# control_board_schematic.net
KiCad netlist of a schematic drawn in EasyEDA
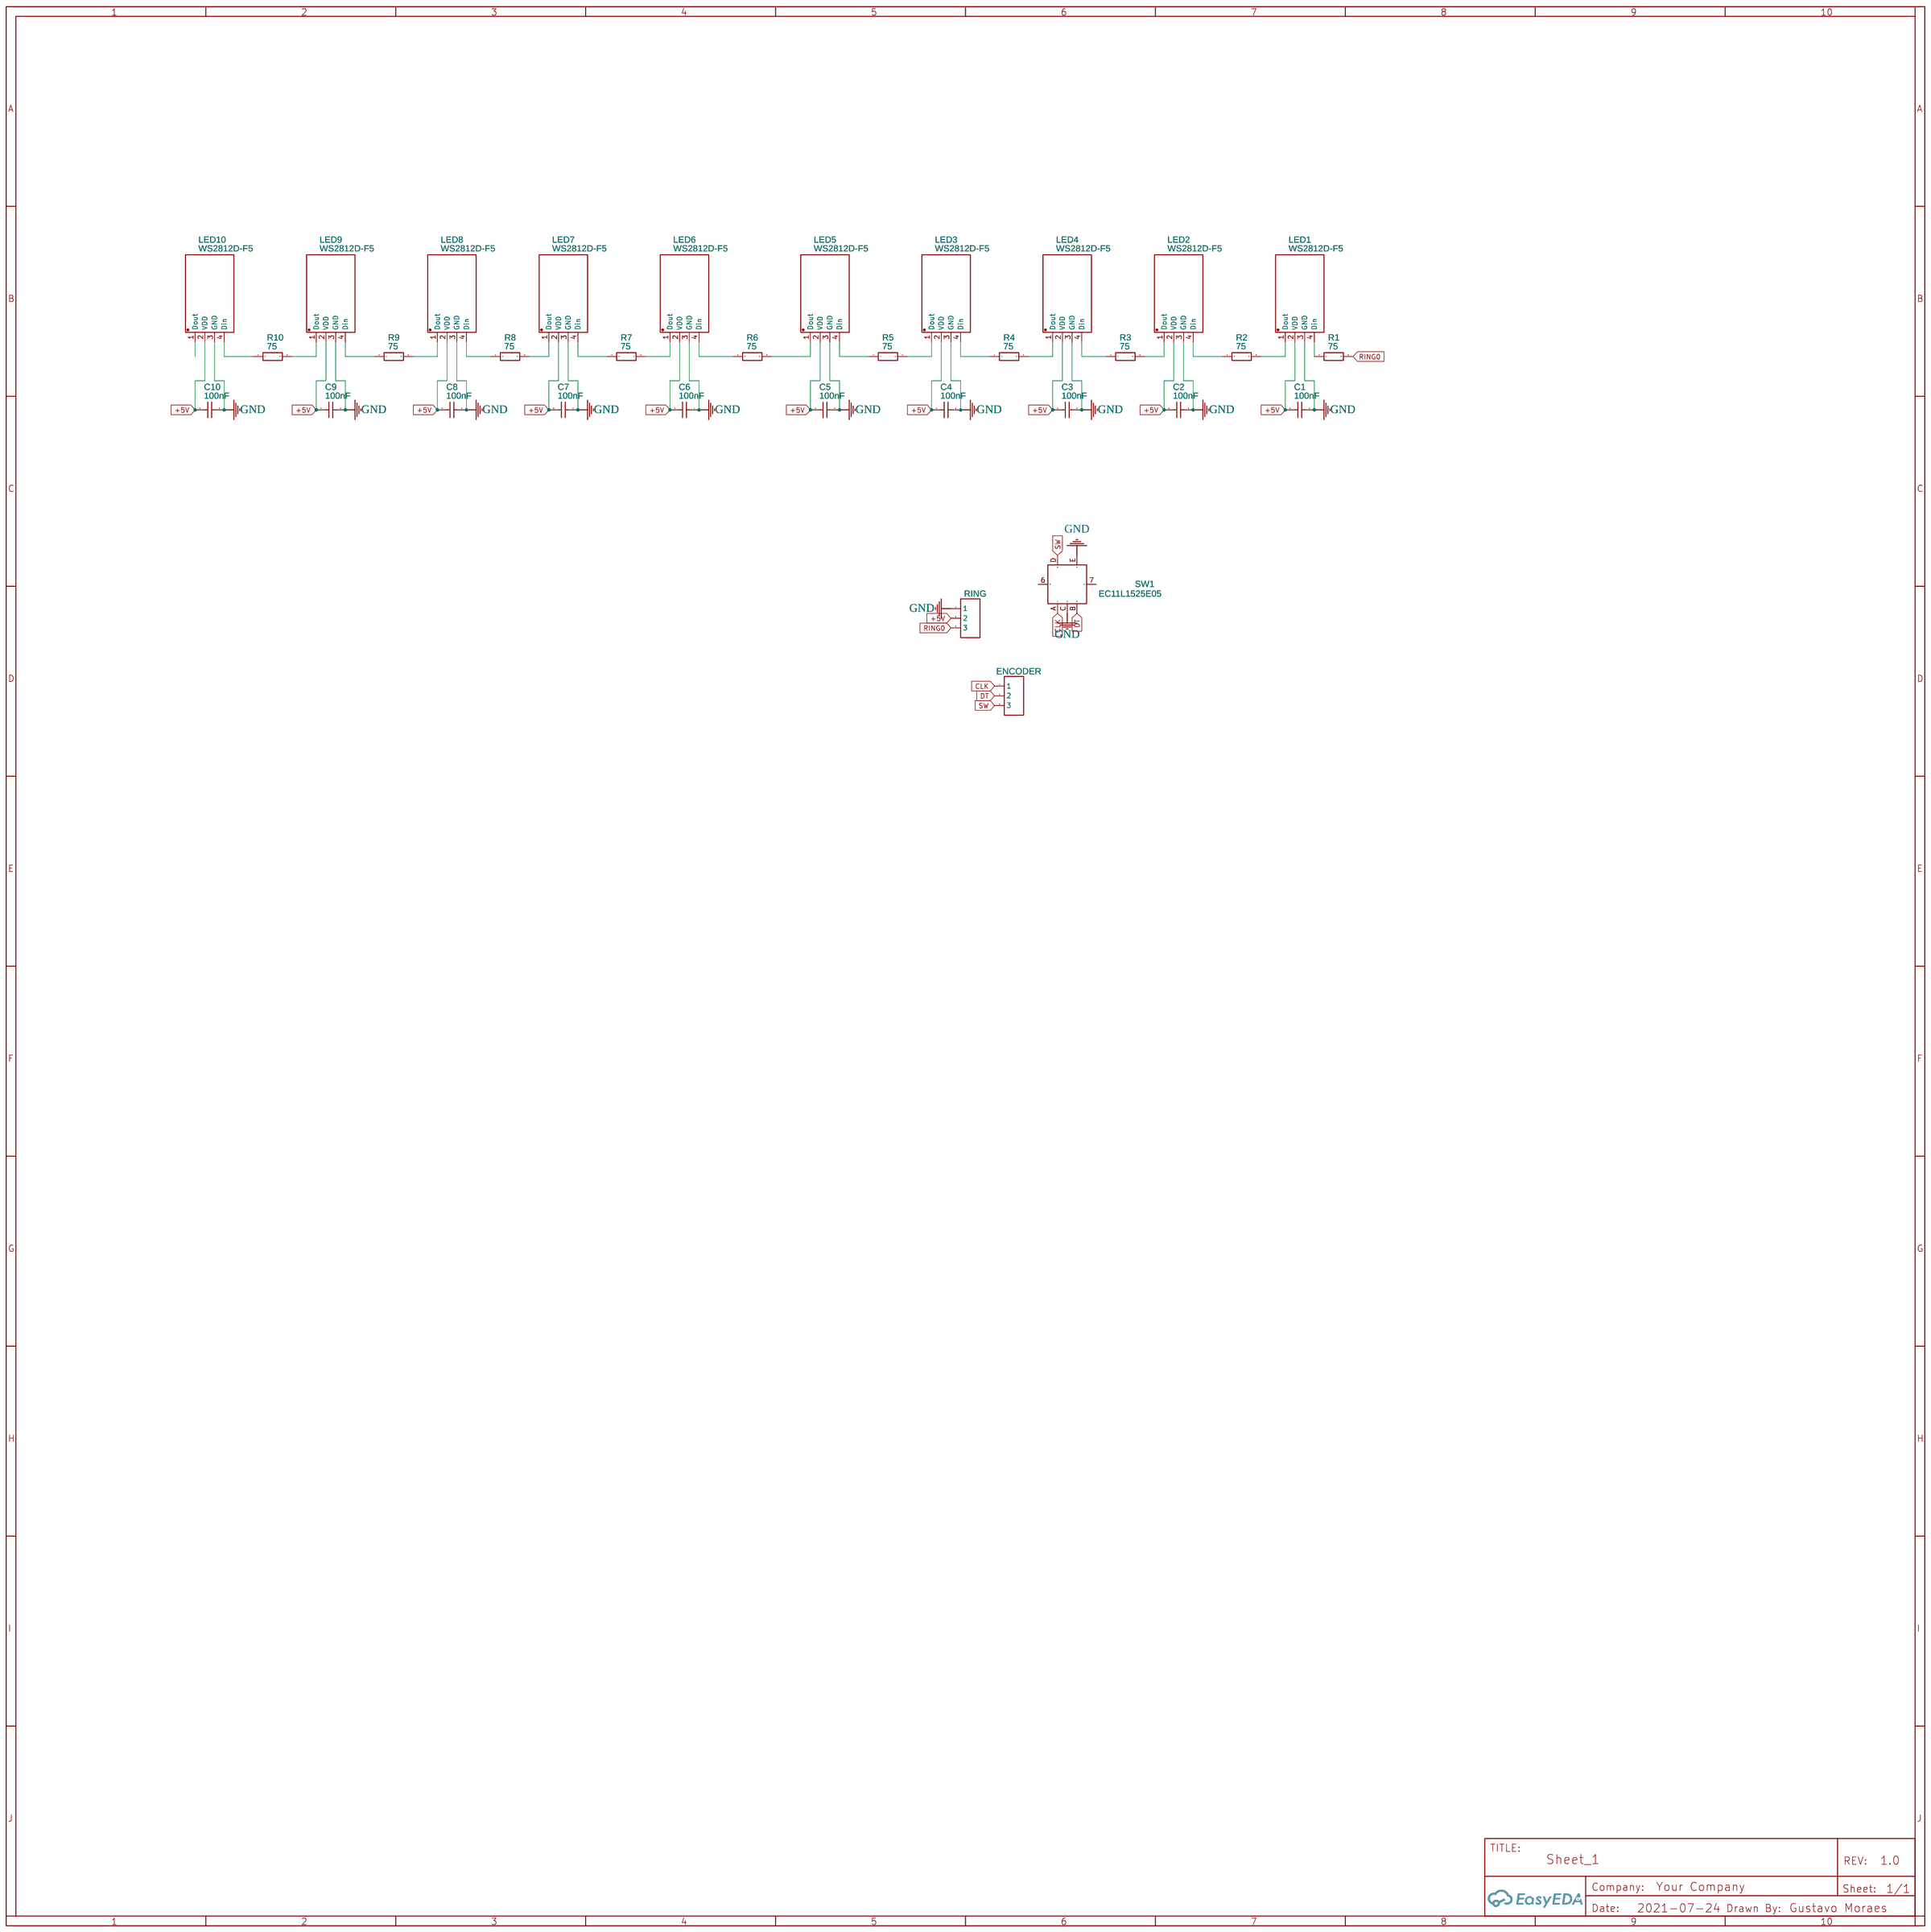
[diagram p0: schematic sheet]

(export (version "E")
  (design (tool "Eeschema 10.0.6"))
  (components
    (comp (ref "C1")
      (value "100nF")
      (fields
        (field (name "BOM_Manufacturer Part") "0603B104K160")
        (field (name "BOM_Supplier Part") "C80516")
      )
      (libsource (lib "") (part "0603B104K160"))
    )
    (comp (ref "C2")
      (value "100nF")
      (fields
        (field (name "BOM_Manufacturer Part") "0603B104K160")
        (field (name "BOM_Supplier Part") "C80516")
      )
      (libsource (lib "") (part "0603B104K160"))
    )
    (comp (ref "C3")
      (value "100nF")
      (fields
        (field (name "BOM_Manufacturer Part") "0603B104K160")
        (field (name "BOM_Supplier Part") "C80516")
      )
      (libsource (lib "") (part "0603B104K160"))
    )
    (comp (ref "C4")
      (value "100nF")
      (fields
        (field (name "BOM_Manufacturer Part") "0603B104K160")
        (field (name "BOM_Supplier Part") "C80516")
      )
      (libsource (lib "") (part "0603B104K160"))
    )
    (comp (ref "C5")
      (value "100nF")
      (fields
        (field (name "BOM_Manufacturer Part") "0603B104K160")
        (field (name "BOM_Supplier Part") "C80516")
      )
      (libsource (lib "") (part "0603B104K160"))
    )
    (comp (ref "C6")
      (value "100nF")
      (fields
        (field (name "BOM_Manufacturer Part") "0603B104K160")
        (field (name "BOM_Supplier Part") "C80516")
      )
      (libsource (lib "") (part "0603B104K160"))
    )
    (comp (ref "C7")
      (value "100nF")
      (fields
        (field (name "BOM_Manufacturer Part") "0603B104K160")
        (field (name "BOM_Supplier Part") "C80516")
      )
      (libsource (lib "") (part "0603B104K160"))
    )
    (comp (ref "C8")
      (value "100nF")
      (fields
        (field (name "BOM_Manufacturer Part") "0603B104K160")
        (field (name "BOM_Supplier Part") "C80516")
      )
      (libsource (lib "") (part "0603B104K160"))
    )
    (comp (ref "C9")
      (value "100nF")
      (fields
        (field (name "BOM_Manufacturer Part") "0603B104K160")
        (field (name "BOM_Supplier Part") "C80516")
      )
      (libsource (lib "") (part "0603B104K160"))
    )
    (comp (ref "C10")
      (value "100nF")
      (fields
        (field (name "BOM_Manufacturer Part") "0603B104K160")
        (field (name "BOM_Supplier Part") "C80516")
      )
      (libsource (lib "") (part "0603B104K160"))
    )
    (comp (ref "ENCODER")
      (value "HDR-M-2.54_1x3")
      (fields (field (name "BOM_Supplier Part") "C180248"))
      (libsource (lib "") (part "HDR-M-2.54_1x3_1"))
    )
    (comp (ref "LED1")
      (value "WS2812D-F5")
      (fields (field (name "BOM_Supplier Part") "C190565"))
      (libsource (lib "") (part "WS2812D-F5"))
    )
    (comp (ref "LED2")
      (value "WS2812D-F5")
      (fields (field (name "BOM_Supplier Part") "C190565"))
      (libsource (lib "") (part "WS2812D-F5"))
    )
    (comp (ref "LED3")
      (value "WS2812D-F5")
      (fields (field (name "BOM_Supplier Part") "C190565"))
      (libsource (lib "") (part "WS2812D-F5"))
    )
    (comp (ref "LED4")
      (value "WS2812D-F5")
      (fields (field (name "BOM_Supplier Part") "C190565"))
      (libsource (lib "") (part "WS2812D-F5"))
    )
    (comp (ref "LED5")
      (value "WS2812D-F5")
      (fields (field (name "BOM_Supplier Part") "C190565"))
      (libsource (lib "") (part "WS2812D-F5"))
    )
    (comp (ref "LED6")
      (value "WS2812D-F5")
      (fields (field (name "BOM_Supplier Part") "C190565"))
      (libsource (lib "") (part "WS2812D-F5"))
    )
    (comp (ref "LED7")
      (value "WS2812D-F5")
      (fields (field (name "BOM_Supplier Part") "C190565"))
      (libsource (lib "") (part "WS2812D-F5"))
    )
    (comp (ref "LED8")
      (value "WS2812D-F5")
      (fields (field (name "BOM_Supplier Part") "C190565"))
      (libsource (lib "") (part "WS2812D-F5"))
    )
    (comp (ref "LED9")
      (value "WS2812D-F5")
      (fields (field (name "BOM_Supplier Part") "C190565"))
      (libsource (lib "") (part "WS2812D-F5"))
    )
    (comp (ref "LED10")
      (value "WS2812D-F5")
      (fields (field (name "BOM_Supplier Part") "C190565"))
      (libsource (lib "") (part "WS2812D-F5"))
    )
    (comp (ref "R1")
      (value "75")
      (fields
        (field (name "BOM_Manufacturer Part") "RC0805JR-0775RL")
        (field (name "BOM_Supplier Part") "C113304")
      )
      (libsource (lib "") (part "RC0805JR-0775RL"))
    )
    (comp (ref "R2")
      (value "75")
      (fields
        (field (name "BOM_Manufacturer Part") "RC0805JR-0775RL")
        (field (name "BOM_Supplier Part") "C113304")
      )
      (libsource (lib "") (part "RC0805JR-0775RL"))
    )
    (comp (ref "R3")
      (value "75")
      (fields
        (field (name "BOM_Manufacturer Part") "RC0805JR-0775RL")
        (field (name "BOM_Supplier Part") "C113304")
      )
      (libsource (lib "") (part "RC0805JR-0775RL"))
    )
    (comp (ref "R4")
      (value "75")
      (fields
        (field (name "BOM_Manufacturer Part") "RC0805JR-0775RL")
        (field (name "BOM_Supplier Part") "C113304")
      )
      (libsource (lib "") (part "RC0805JR-0775RL"))
    )
    (comp (ref "R5")
      (value "75")
      (fields
        (field (name "BOM_Manufacturer Part") "RC0805JR-0775RL")
        (field (name "BOM_Supplier Part") "C113304")
      )
      (libsource (lib "") (part "RC0805JR-0775RL"))
    )
    (comp (ref "R6")
      (value "75")
      (fields
        (field (name "BOM_Manufacturer Part") "RC0805JR-0775RL")
        (field (name "BOM_Supplier Part") "C113304")
      )
      (libsource (lib "") (part "RC0805JR-0775RL"))
    )
    (comp (ref "R7")
      (value "75")
      (fields
        (field (name "BOM_Manufacturer Part") "RC0805JR-0775RL")
        (field (name "BOM_Supplier Part") "C113304")
      )
      (libsource (lib "") (part "RC0805JR-0775RL"))
    )
    (comp (ref "R8")
      (value "75")
      (fields
        (field (name "BOM_Manufacturer Part") "RC0805JR-0775RL")
        (field (name "BOM_Supplier Part") "C113304")
      )
      (libsource (lib "") (part "RC0805JR-0775RL"))
    )
    (comp (ref "R9")
      (value "75")
      (fields
        (field (name "BOM_Manufacturer Part") "RC0805JR-0775RL")
        (field (name "BOM_Supplier Part") "C113304")
      )
      (libsource (lib "") (part "RC0805JR-0775RL"))
    )
    (comp (ref "R10")
      (value "75")
      (fields
        (field (name "BOM_Manufacturer Part") "RC0805JR-0775RL")
        (field (name "BOM_Supplier Part") "C113304")
      )
      (libsource (lib "") (part "RC0805JR-0775RL"))
    )
    (comp (ref "RING")
      (value "HDR-M-2.54_1x3")
      (fields (field (name "BOM_Supplier Part") "C180248"))
      (libsource (lib "") (part "HDR-M-2.54_1x3"))
    )
    (comp (ref "SW1")
      (value "EC11L1525E05")
      (fields (field (name "BOM_Supplier Part") "C2687298"))
      (libsource (lib "") (part "EC11L1525E05"))
    )
  )
  (nets
    (net (code "1") (name "+5V") (class "Default")
      (node (ref "C1") (pin "2") (pinfunction "2_2") (pintype "input"))
      (node (ref "C10") (pin "2") (pinfunction "2_2") (pintype "input"))
      (node (ref "C2") (pin "2") (pinfunction "2_2") (pintype "input"))
      (node (ref "C3") (pin "2") (pinfunction "2_2") (pintype "input"))
      (node (ref "C4") (pin "2") (pinfunction "2_2") (pintype "input"))
      (node (ref "C5") (pin "2") (pinfunction "2_2") (pintype "input"))
      (node (ref "C6") (pin "2") (pinfunction "2_2") (pintype "input"))
      (node (ref "C7") (pin "2") (pinfunction "2_2") (pintype "input"))
      (node (ref "C8") (pin "2") (pinfunction "2_2") (pintype "input"))
      (node (ref "C9") (pin "2") (pinfunction "2_2") (pintype "input"))
      (node (ref "LED1") (pin "2") (pinfunction "VDD_2") (pintype "unspecified"))
      (node (ref "LED10") (pin "2") (pinfunction "VDD_2") (pintype "unspecified"))
      (node (ref "LED2") (pin "2") (pinfunction "VDD_2") (pintype "unspecified"))
      (node (ref "LED3") (pin "2") (pinfunction "VDD_2") (pintype "unspecified"))
      (node (ref "LED4") (pin "2") (pinfunction "VDD_2") (pintype "unspecified"))
      (node (ref "LED5") (pin "2") (pinfunction "VDD_2") (pintype "unspecified"))
      (node (ref "LED6") (pin "2") (pinfunction "VDD_2") (pintype "unspecified"))
      (node (ref "LED7") (pin "2") (pinfunction "VDD_2") (pintype "unspecified"))
      (node (ref "LED8") (pin "2") (pinfunction "VDD_2") (pintype "unspecified"))
      (node (ref "LED9") (pin "2") (pinfunction "VDD_2") (pintype "unspecified"))
      (node (ref "RING") (pin "2") (pinfunction "2_2") (pintype "input"))
    )
    (net (code "2") (name "CLK") (class "Default")
      (node (ref "ENCODER") (pin "1") (pinfunction "1_1") (pintype "input"))
      (node (ref "SW1") (pin "A") (pinfunction "A_A") (pintype "unspecified"))
    )
    (net (code "3") (name "DT") (class "Default")
      (node (ref "ENCODER") (pin "2") (pinfunction "2_2") (pintype "input"))
      (node (ref "SW1") (pin "B") (pinfunction "B_B") (pintype "unspecified"))
    )
    (net (code "4") (name "GND") (class "Default")
      (node (ref "C1") (pin "1") (pinfunction "1_1") (pintype "input"))
      (node (ref "C10") (pin "1") (pinfunction "1_1") (pintype "input"))
      (node (ref "C2") (pin "1") (pinfunction "1_1") (pintype "input"))
      (node (ref "C3") (pin "1") (pinfunction "1_1") (pintype "input"))
      (node (ref "C4") (pin "1") (pinfunction "1_1") (pintype "input"))
      (node (ref "C5") (pin "1") (pinfunction "1_1") (pintype "input"))
      (node (ref "C6") (pin "1") (pinfunction "1_1") (pintype "input"))
      (node (ref "C7") (pin "1") (pinfunction "1_1") (pintype "input"))
      (node (ref "C8") (pin "1") (pinfunction "1_1") (pintype "input"))
      (node (ref "C9") (pin "1") (pinfunction "1_1") (pintype "input"))
      (node (ref "LED1") (pin "3") (pinfunction "GND_3") (pintype "unspecified"))
      (node (ref "LED10") (pin "3") (pinfunction "GND_3") (pintype "unspecified"))
      (node (ref "LED2") (pin "3") (pinfunction "GND_3") (pintype "unspecified"))
      (node (ref "LED3") (pin "3") (pinfunction "GND_3") (pintype "unspecified"))
      (node (ref "LED4") (pin "3") (pinfunction "GND_3") (pintype "unspecified"))
      (node (ref "LED5") (pin "3") (pinfunction "GND_3") (pintype "unspecified"))
      (node (ref "LED6") (pin "3") (pinfunction "GND_3") (pintype "unspecified"))
      (node (ref "LED7") (pin "3") (pinfunction "GND_3") (pintype "unspecified"))
      (node (ref "LED8") (pin "3") (pinfunction "GND_3") (pintype "unspecified"))
      (node (ref "LED9") (pin "3") (pinfunction "GND_3") (pintype "unspecified"))
      (node (ref "RING") (pin "1") (pinfunction "1_1") (pintype "input"))
      (node (ref "SW1") (pin "C") (pinfunction "C_C") (pintype "unspecified"))
      (node (ref "SW1") (pin "E") (pinfunction "E_E") (pintype "unspecified"))
    )
    (net (code "5") (name "Net-(LED1-Din)") (class "Default")
      (node (ref "LED1") (pin "4") (pinfunction "Din_4") (pintype "unspecified"))
      (node (ref "R1") (pin "1") (pinfunction "1_1") (pintype "input"))
    )
    (net (code "6") (name "Net-(LED1-Dout)") (class "Default")
      (node (ref "LED1") (pin "1") (pinfunction "Dout_1") (pintype "unspecified"))
      (node (ref "R2") (pin "2") (pinfunction "2_2") (pintype "input"))
    )
    (net (code "7") (name "Net-(LED2-Din)") (class "Default")
      (node (ref "LED2") (pin "4") (pinfunction "Din_4") (pintype "unspecified"))
      (node (ref "R2") (pin "1") (pinfunction "1_1") (pintype "input"))
    )
    (net (code "8") (name "Net-(LED2-Dout)") (class "Default")
      (node (ref "LED2") (pin "1") (pinfunction "Dout_1") (pintype "unspecified"))
      (node (ref "R3") (pin "2") (pinfunction "2_2") (pintype "input"))
    )
    (net (code "9") (name "Net-(LED3-Din)") (class "Default")
      (node (ref "LED3") (pin "4") (pinfunction "Din_4") (pintype "unspecified"))
      (node (ref "R4") (pin "1") (pinfunction "1_1") (pintype "input"))
    )
    (net (code "10") (name "Net-(LED3-Dout)") (class "Default")
      (node (ref "LED3") (pin "1") (pinfunction "Dout_1") (pintype "unspecified"))
      (node (ref "R5") (pin "2") (pinfunction "2_2") (pintype "input"))
    )
    (net (code "11") (name "Net-(LED4-Din)") (class "Default")
      (node (ref "LED4") (pin "4") (pinfunction "Din_4") (pintype "unspecified"))
      (node (ref "R3") (pin "1") (pinfunction "1_1") (pintype "input"))
    )
    (net (code "12") (name "Net-(LED4-Dout)") (class "Default")
      (node (ref "LED4") (pin "1") (pinfunction "Dout_1") (pintype "unspecified"))
      (node (ref "R4") (pin "2") (pinfunction "2_2") (pintype "input"))
    )
    (net (code "13") (name "Net-(LED5-Din)") (class "Default")
      (node (ref "LED5") (pin "4") (pinfunction "Din_4") (pintype "unspecified"))
      (node (ref "R5") (pin "1") (pinfunction "1_1") (pintype "input"))
    )
    (net (code "14") (name "Net-(LED5-Dout)") (class "Default")
      (node (ref "LED5") (pin "1") (pinfunction "Dout_1") (pintype "unspecified"))
      (node (ref "R6") (pin "2") (pinfunction "2_2") (pintype "input"))
    )
    (net (code "15") (name "Net-(LED6-Din)") (class "Default")
      (node (ref "LED6") (pin "4") (pinfunction "Din_4") (pintype "unspecified"))
      (node (ref "R6") (pin "1") (pinfunction "1_1") (pintype "input"))
    )
    (net (code "16") (name "Net-(LED6-Dout)") (class "Default")
      (node (ref "LED6") (pin "1") (pinfunction "Dout_1") (pintype "unspecified"))
      (node (ref "R7") (pin "2") (pinfunction "2_2") (pintype "input"))
    )
    (net (code "17") (name "Net-(LED7-Din)") (class "Default")
      (node (ref "LED7") (pin "4") (pinfunction "Din_4") (pintype "unspecified"))
      (node (ref "R7") (pin "1") (pinfunction "1_1") (pintype "input"))
    )
    (net (code "18") (name "Net-(LED7-Dout)") (class "Default")
      (node (ref "LED7") (pin "1") (pinfunction "Dout_1") (pintype "unspecified"))
      (node (ref "R8") (pin "2") (pinfunction "2_2") (pintype "input"))
    )
    (net (code "19") (name "Net-(LED8-Din)") (class "Default")
      (node (ref "LED8") (pin "4") (pinfunction "Din_4") (pintype "unspecified"))
      (node (ref "R8") (pin "1") (pinfunction "1_1") (pintype "input"))
    )
    (net (code "20") (name "Net-(LED8-Dout)") (class "Default")
      (node (ref "LED8") (pin "1") (pinfunction "Dout_1") (pintype "unspecified"))
      (node (ref "R9") (pin "2") (pinfunction "2_2") (pintype "input"))
    )
    (net (code "21") (name "Net-(LED9-Din)") (class "Default")
      (node (ref "LED9") (pin "4") (pinfunction "Din_4") (pintype "unspecified"))
      (node (ref "R9") (pin "1") (pinfunction "1_1") (pintype "input"))
    )
    (net (code "22") (name "Net-(LED9-Dout)") (class "Default")
      (node (ref "LED9") (pin "1") (pinfunction "Dout_1") (pintype "unspecified"))
      (node (ref "R10") (pin "2") (pinfunction "2_2") (pintype "input"))
    )
    (net (code "23") (name "Net-(LED10-Din)") (class "Default")
      (node (ref "LED10") (pin "4") (pinfunction "Din_4") (pintype "unspecified"))
      (node (ref "R10") (pin "1") (pinfunction "1_1") (pintype "input"))
    )
    (net (code "24") (name "RING0") (class "Default")
      (node (ref "R1") (pin "2") (pinfunction "2_2") (pintype "input"))
      (node (ref "RING") (pin "3") (pinfunction "3_3") (pintype "input"))
    )
    (net (code "25") (name "SW") (class "Default")
      (node (ref "ENCODER") (pin "3") (pinfunction "3_3") (pintype "input"))
      (node (ref "SW1") (pin "D") (pinfunction "D_D") (pintype "unspecified"))
    )
    (net (code "26") (name "unconnected-(LED10-Dout-Pad1)") (class "Default")
      (node (ref "LED10") (pin "1") (pinfunction "Dout_1") (pintype "unspecified"))
    )
    (net (code "27") (name "unconnected-(SW1-EH-Pad6)") (class "Default")
      (node (ref "SW1") (pin "6") (pinfunction "EH_6") (pintype "unspecified"))
    )
    (net (code "28") (name "unconnected-(SW1-EH-Pad7)") (class "Default")
      (node (ref "SW1") (pin "7") (pinfunction "EH_7") (pintype "unspecified"))
    )
  )
)
